# NFC-WiFi.net
KiCad netlist of a schematic drawn in EAGLE
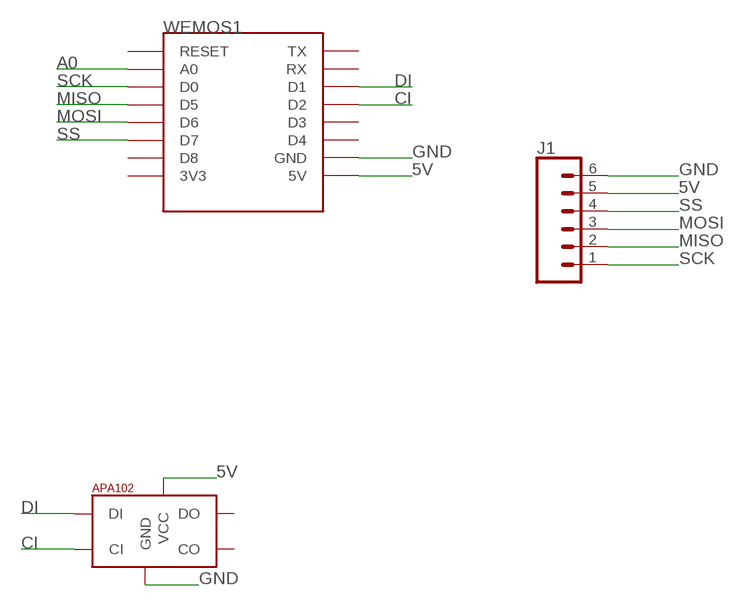
[diagram p0: schematic, sheet 1]

(export (version "E")
  (design (tool "Eeschema 10.0.6"))
  (components
    (comp (ref "J1")
      (value "CONN_06SILK_FEMALE_PTH")
      (footprint "eagle-import:1X06")
      (libsource (lib "eagle-import") (part "CONN_06SILK_FEMALE_PTH"))
    )
    (comp (ref "U$1")
      (value "APA1025050")
      (footprint "eagle-import:APA102_5050")
      (libsource (lib "eagle-import") (part "APA1025050"))
    )
    (comp (ref "WEMOS1")
      (value "WEMOS-D1-MINI")
      (footprint "eagle-import:WEMOS-D1-MINI")
      (libsource (lib "eagle-import") (part "WEMOS-D1-MINI"))
    )
  )
  (nets
    (net (code "1") (name "/5V") (class "Default")
      (node (ref "J1") (pin "5") (pinfunction "5_5") (pintype "passive"))
      (node (ref "U$1") (pin "1") (pinfunction "VCC_1") (pintype "bidirectional"))
      (node (ref "WEMOS1") (pin "5V") (pinfunction "5V_5V") (pintype "bidirectional"))
    )
    (net (code "2") (name "/A0") (class "Default")
      (node (ref "WEMOS1") (pin "A0") (pinfunction "A0_A0") (pintype "bidirectional"))
    )
    (net (code "3") (name "/CI") (class "Default")
      (node (ref "U$1") (pin "5") (pinfunction "CI_5") (pintype "bidirectional"))
      (node (ref "WEMOS1") (pin "D2") (pinfunction "D2_D2") (pintype "bidirectional"))
    )
    (net (code "4") (name "/DI") (class "Default")
      (node (ref "U$1") (pin "4") (pinfunction "DI_4") (pintype "bidirectional"))
      (node (ref "WEMOS1") (pin "D1") (pinfunction "D1_D1") (pintype "bidirectional"))
    )
    (net (code "5") (name "/GND") (class "Default")
      (node (ref "J1") (pin "6") (pinfunction "6_6") (pintype "passive"))
      (node (ref "U$1") (pin "6") (pinfunction "GND_6") (pintype "bidirectional"))
      (node (ref "WEMOS1") (pin "GND") (pinfunction "GND_GND") (pintype "bidirectional"))
    )
    (net (code "6") (name "/MISO") (class "Default")
      (node (ref "J1") (pin "2") (pinfunction "2_2") (pintype "passive"))
      (node (ref "WEMOS1") (pin "D5") (pinfunction "D5_D5") (pintype "bidirectional"))
    )
    (net (code "7") (name "/MOSI") (class "Default")
      (node (ref "J1") (pin "3") (pinfunction "3_3") (pintype "passive"))
      (node (ref "WEMOS1") (pin "D6") (pinfunction "D6_D6") (pintype "bidirectional"))
    )
    (net (code "8") (name "/SCK") (class "Default")
      (node (ref "J1") (pin "1") (pinfunction "1_1") (pintype "passive"))
      (node (ref "WEMOS1") (pin "D0") (pinfunction "D0_D0") (pintype "bidirectional"))
    )
    (net (code "9") (name "/SS") (class "Default")
      (node (ref "J1") (pin "4") (pinfunction "4_4") (pintype "passive"))
      (node (ref "WEMOS1") (pin "D7") (pinfunction "D7_D7") (pintype "bidirectional"))
    )
    (net (code "10") (name "unconnected-(U$1-CO-Pad2)") (class "Default")
      (node (ref "U$1") (pin "2") (pinfunction "CO_2") (pintype "bidirectional"))
    )
    (net (code "11") (name "unconnected-(U$1-DO-Pad3)") (class "Default")
      (node (ref "U$1") (pin "3") (pinfunction "DO_3") (pintype "bidirectional"))
    )
    (net (code "12") (name "unconnected-(WEMOS1-Pad3V3)") (class "Default")
      (node (ref "WEMOS1") (pin "3V3") (pinfunction "3V3_3V3") (pintype "bidirectional"))
    )
    (net (code "13") (name "unconnected-(WEMOS1-PadD3)") (class "Default")
      (node (ref "WEMOS1") (pin "D3") (pinfunction "D3_D3") (pintype "bidirectional"))
    )
    (net (code "14") (name "unconnected-(WEMOS1-PadD4)") (class "Default")
      (node (ref "WEMOS1") (pin "D4") (pinfunction "D4_D4") (pintype "bidirectional"))
    )
    (net (code "15") (name "unconnected-(WEMOS1-PadD8)") (class "Default")
      (node (ref "WEMOS1") (pin "D8") (pinfunction "D8_D8") (pintype "bidirectional"))
    )
    (net (code "16") (name "unconnected-(WEMOS1-PadRESET)") (class "Default")
      (node (ref "WEMOS1") (pin "RESET") (pinfunction "RESET_RESET") (pintype "bidirectional"))
    )
    (net (code "17") (name "unconnected-(WEMOS1-PadRX)") (class "Default")
      (node (ref "WEMOS1") (pin "RX") (pinfunction "RX_RX") (pintype "bidirectional"))
    )
    (net (code "18") (name "unconnected-(WEMOS1-PadTX)") (class "Default")
      (node (ref "WEMOS1") (pin "TX") (pinfunction "TX_TX") (pintype "bidirectional"))
    )
  )
)
